# ROMSIMMProgrammer.net
KiCad netlist of a schematic drawn in EAGLE
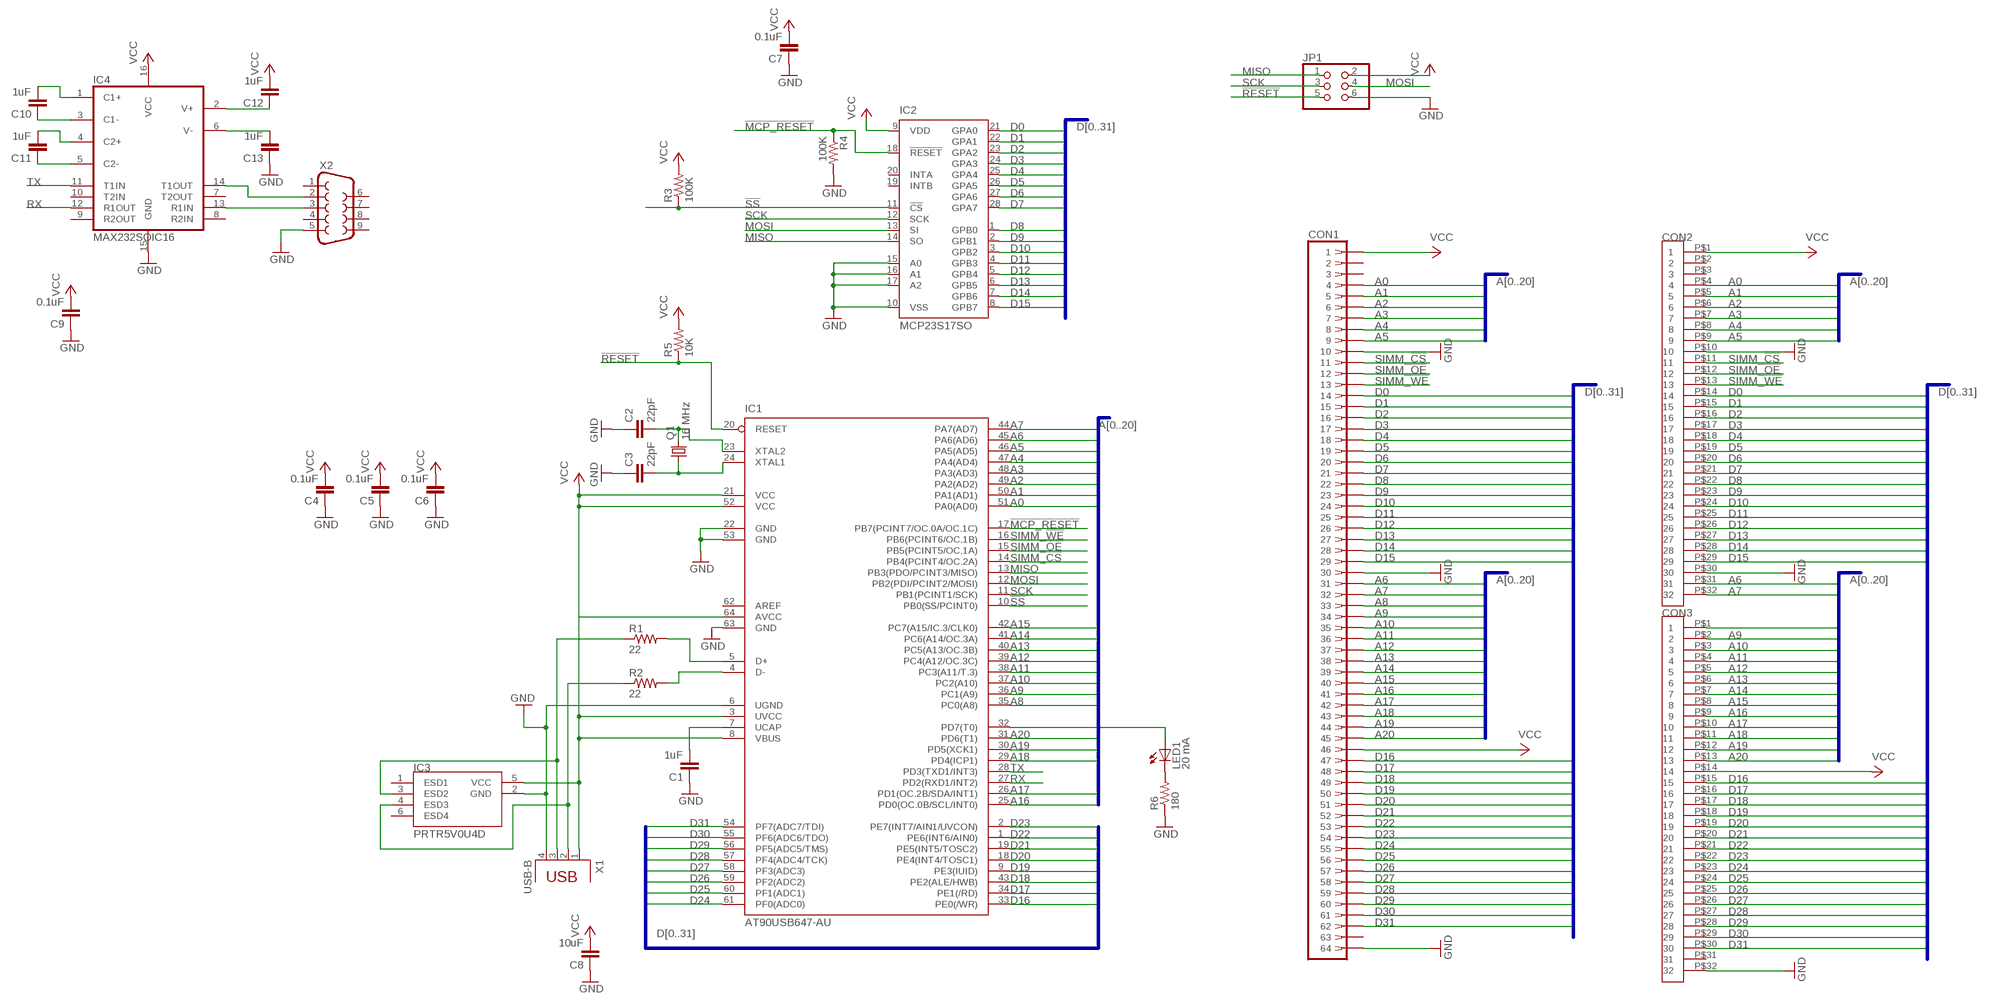
[diagram p0: schematic, sheet 1]

(export (version "E")
  (design (tool "Eeschema 10.0.6"))
  (components
    (comp (ref "C1")
      (value "1uF")
      (footprint "eagle-import:C0805")
      (libsource (lib "eagle-import") (part "C-EUC0805"))
    )
    (comp (ref "C2")
      (value "22pF")
      (footprint "eagle-import:C0805")
      (libsource (lib "eagle-import") (part "C-EUC0805"))
    )
    (comp (ref "C3")
      (value "22pF")
      (footprint "eagle-import:C0805")
      (libsource (lib "eagle-import") (part "C-EUC0805"))
    )
    (comp (ref "C4")
      (value "0.1uF")
      (footprint "eagle-import:C0805")
      (libsource (lib "eagle-import") (part "C-EUC0805"))
    )
    (comp (ref "C5")
      (value "0.1uF")
      (footprint "eagle-import:C0805")
      (libsource (lib "eagle-import") (part "C-EUC0805"))
    )
    (comp (ref "C6")
      (value "0.1uF")
      (footprint "eagle-import:C0805")
      (libsource (lib "eagle-import") (part "C-EUC0805"))
    )
    (comp (ref "C7")
      (value "0.1uF")
      (footprint "eagle-import:C0805")
      (libsource (lib "eagle-import") (part "C-EUC0805"))
    )
    (comp (ref "C8")
      (value "10uF")
      (footprint "eagle-import:C0805")
      (libsource (lib "eagle-import") (part "C-EUC0805"))
    )
    (comp (ref "C9")
      (value "0.1uF")
      (footprint "eagle-import:C0805")
      (libsource (lib "eagle-import") (part "C-EUC0805"))
    )
    (comp (ref "C10")
      (value "1uF")
      (footprint "eagle-import:C0805")
      (libsource (lib "eagle-import") (part "C-EUC0805"))
    )
    (comp (ref "C11")
      (value "1uF")
      (footprint "eagle-import:C0805")
      (libsource (lib "eagle-import") (part "C-EUC0805"))
    )
    (comp (ref "C12")
      (value "1uF")
      (footprint "eagle-import:C0805")
      (libsource (lib "eagle-import") (part "C-EUC0805"))
    )
    (comp (ref "C13")
      (value "1uF")
      (footprint "eagle-import:C0805")
      (libsource (lib "eagle-import") (part "C-EUC0805"))
    )
    (comp (ref "CON1")
      (value "SIMM64")
      (footprint "eagle-import:822032-2")
      (libsource (lib "eagle-import") (part "SIMM64"))
    )
    (comp (ref "CON2")
      (value "SMS-132-01-G-S")
      (footprint "eagle-import:SMS-132-01-G-S")
      (libsource (lib "eagle-import") (part "SMS-132-01-G-S"))
    )
    (comp (ref "CON3")
      (value "SMS-132-01-G-S")
      (footprint "eagle-import:SMS-132-01-G-S")
      (libsource (lib "eagle-import") (part "SMS-132-01-G-S"))
    )
    (comp (ref "IC1")
      (value "AT90USB647-AU")
      (footprint "eagle-import:TQFP64")
      (libsource (lib "eagle-import") (part "AT90USB647-AU"))
    )
    (comp (ref "IC2")
      (value "MCP23S17SO")
      (footprint "eagle-import:SO28W")
      (fields (field (name "MF") "MICROCHIP") (field (name "MPN") "MCP23S17-E/SO"))
      (libsource (lib "eagle-import") (part "MCP23S17SO"))
    )
    (comp (ref "IC3")
      (value "PRTR5V0U4D")
      (footprint "eagle-import:SOT457R_PHILIPS")
      (libsource (lib "eagle-import") (part "PRTR5V0U4D"))
    )
    (comp (ref "IC4")
      (value "MAX232SOIC16")
      (footprint "eagle-import:SO016")
      (libsource (lib "eagle-import") (part "MAX232SOIC16"))
    )
    (comp (ref "JP1")
      (value "PINHD-2X3")
      (footprint "eagle-import:2X03")
      (libsource (lib "eagle-import") (part "PINHD-2X3"))
    )
    (comp (ref "LED1")
      (value "20 mA")
      (footprint "eagle-import:CHIP-LED0805")
      (libsource (lib "eagle-import") (part "LEDCHIP-LED0805"))
    )
    (comp (ref "Q1")
      (value "16 MHz")
      (footprint "eagle-import:HC49UP")
      (libsource (lib "eagle-import") (part "CRYSTALHC49UP"))
    )
    (comp (ref "R1")
      (value "22")
      (footprint "eagle-import:R0805")
      (libsource (lib "eagle-import") (part "R-US_R0805"))
    )
    (comp (ref "R2")
      (value "22")
      (footprint "eagle-import:R0805")
      (libsource (lib "eagle-import") (part "R-US_R0805"))
    )
    (comp (ref "R3")
      (value "100K")
      (footprint "eagle-import:R0805")
      (libsource (lib "eagle-import") (part "R-US_R0805"))
    )
    (comp (ref "R4")
      (value "100K")
      (footprint "eagle-import:R0805")
      (libsource (lib "eagle-import") (part "R-US_R0805"))
    )
    (comp (ref "R5")
      (value "10K")
      (footprint "eagle-import:R0805")
      (libsource (lib "eagle-import") (part "R-US_R0805"))
    )
    (comp (ref "R6")
      (value "180")
      (footprint "eagle-import:R0805")
      (libsource (lib "eagle-import") (part "R-US_R0805"))
    )
    (comp (ref "X1")
      (value "USB-B")
      (footprint "eagle-import:PN61729")
      (libsource (lib "eagle-import") (part "PN61729"))
    )
    (comp (ref "X2")
      (value "DB9FEMALE")
      (footprint "eagle-import:DB9")
      (libsource (lib "eagle-import") (part "DB9FEMALE"))
    )
  )
  (nets
    (net (code "1") (name "/A0") (class "Default")
      (node (ref "CON1") (pin "4") (pinfunction "4_4") (pintype "passive"))
      (node (ref "CON2") (pin "P$4") (pinfunction "4_P$4") (pintype "bidirectional"))
      (node (ref "IC1") (pin "51") (pinfunction "PA0(AD0)_51") (pintype "bidirectional"))
    )
    (net (code "2") (name "/A1") (class "Default")
      (node (ref "CON1") (pin "5") (pinfunction "5_5") (pintype "passive"))
      (node (ref "CON2") (pin "P$5") (pinfunction "5_P$5") (pintype "bidirectional"))
      (node (ref "IC1") (pin "50") (pinfunction "PA1(AD1)_50") (pintype "bidirectional"))
    )
    (net (code "3") (name "/A2") (class "Default")
      (node (ref "CON1") (pin "6") (pinfunction "6_6") (pintype "passive"))
      (node (ref "CON2") (pin "P$6") (pinfunction "6_P$6") (pintype "bidirectional"))
      (node (ref "IC1") (pin "49") (pinfunction "PA2(AD2)_49") (pintype "bidirectional"))
    )
    (net (code "4") (name "/A3") (class "Default")
      (node (ref "CON1") (pin "7") (pinfunction "7_7") (pintype "passive"))
      (node (ref "CON2") (pin "P$7") (pinfunction "7_P$7") (pintype "bidirectional"))
      (node (ref "IC1") (pin "48") (pinfunction "PA3(AD3)_48") (pintype "bidirectional"))
    )
    (net (code "5") (name "/A4") (class "Default")
      (node (ref "CON1") (pin "8") (pinfunction "8_8") (pintype "passive"))
      (node (ref "CON2") (pin "P$8") (pinfunction "8_P$8") (pintype "bidirectional"))
      (node (ref "IC1") (pin "47") (pinfunction "PA4(AD4)_47") (pintype "bidirectional"))
    )
    (net (code "6") (name "/A5") (class "Default")
      (node (ref "CON1") (pin "9") (pinfunction "9_9") (pintype "passive"))
      (node (ref "CON2") (pin "P$9") (pinfunction "9_P$9") (pintype "bidirectional"))
      (node (ref "IC1") (pin "46") (pinfunction "PA5(AD5)_46") (pintype "bidirectional"))
    )
    (net (code "7") (name "/A6") (class "Default")
      (node (ref "CON1") (pin "31") (pinfunction "31_31") (pintype "passive"))
      (node (ref "CON2") (pin "P$31") (pinfunction "31_P$31") (pintype "bidirectional"))
      (node (ref "IC1") (pin "45") (pinfunction "PA6(AD6)_45") (pintype "bidirectional"))
    )
    (net (code "8") (name "/A7") (class "Default")
      (node (ref "CON1") (pin "32") (pinfunction "32_32") (pintype "passive"))
      (node (ref "CON2") (pin "P$32") (pinfunction "32_P$32") (pintype "bidirectional"))
      (node (ref "IC1") (pin "44") (pinfunction "PA7(AD7)_44") (pintype "bidirectional"))
    )
    (net (code "9") (name "/A8") (class "Default")
      (node (ref "CON1") (pin "33") (pinfunction "33_33") (pintype "passive"))
      (node (ref "CON3") (pin "P$1") (pinfunction "1_P$1") (pintype "bidirectional"))
      (node (ref "IC1") (pin "35") (pinfunction "PC0(A8)_35") (pintype "bidirectional"))
    )
    (net (code "10") (name "/A9") (class "Default")
      (node (ref "CON1") (pin "34") (pinfunction "34_34") (pintype "passive"))
      (node (ref "CON3") (pin "P$2") (pinfunction "2_P$2") (pintype "bidirectional"))
      (node (ref "IC1") (pin "36") (pinfunction "PC1(A9)_36") (pintype "bidirectional"))
    )
    (net (code "11") (name "/A10") (class "Default")
      (node (ref "CON1") (pin "35") (pinfunction "35_35") (pintype "passive"))
      (node (ref "CON3") (pin "P$3") (pinfunction "3_P$3") (pintype "bidirectional"))
      (node (ref "IC1") (pin "37") (pinfunction "PC2(A10)_37") (pintype "bidirectional"))
    )
    (net (code "12") (name "/A11") (class "Default")
      (node (ref "CON1") (pin "36") (pinfunction "36_36") (pintype "passive"))
      (node (ref "CON3") (pin "P$4") (pinfunction "4_P$4") (pintype "bidirectional"))
      (node (ref "IC1") (pin "38") (pinfunction "PC3(A11/T.3)_38") (pintype "bidirectional"))
    )
    (net (code "13") (name "/A12") (class "Default")
      (node (ref "CON1") (pin "37") (pinfunction "37_37") (pintype "passive"))
      (node (ref "CON3") (pin "P$5") (pinfunction "5_P$5") (pintype "bidirectional"))
      (node (ref "IC1") (pin "39") (pinfunction "PC4(A12/OC.3C)_39") (pintype "bidirectional"))
    )
    (net (code "14") (name "/A13") (class "Default")
      (node (ref "CON1") (pin "38") (pinfunction "38_38") (pintype "passive"))
      (node (ref "CON3") (pin "P$6") (pinfunction "6_P$6") (pintype "bidirectional"))
      (node (ref "IC1") (pin "40") (pinfunction "PC5(A13/OC.3B)_40") (pintype "bidirectional"))
    )
    (net (code "15") (name "/A14") (class "Default")
      (node (ref "CON1") (pin "39") (pinfunction "39_39") (pintype "passive"))
      (node (ref "CON3") (pin "P$7") (pinfunction "7_P$7") (pintype "bidirectional"))
      (node (ref "IC1") (pin "41") (pinfunction "PC6(A14/OC.3A)_41") (pintype "bidirectional"))
    )
    (net (code "16") (name "/A15") (class "Default")
      (node (ref "CON1") (pin "40") (pinfunction "40_40") (pintype "passive"))
      (node (ref "CON3") (pin "P$8") (pinfunction "8_P$8") (pintype "bidirectional"))
      (node (ref "IC1") (pin "42") (pinfunction "PC7(A15/IC.3/CLK0)_42") (pintype "bidirectional"))
    )
    (net (code "17") (name "/A16") (class "Default")
      (node (ref "CON1") (pin "41") (pinfunction "41_41") (pintype "passive"))
      (node (ref "CON3") (pin "P$9") (pinfunction "9_P$9") (pintype "bidirectional"))
      (node (ref "IC1") (pin "25") (pinfunction "PD0(OC.0B/SCL/INT0)_25") (pintype "bidirectional"))
    )
    (net (code "18") (name "/A17") (class "Default")
      (node (ref "CON1") (pin "42") (pinfunction "42_42") (pintype "passive"))
      (node (ref "CON3") (pin "P$10") (pinfunction "10_P$10") (pintype "bidirectional"))
      (node (ref "IC1") (pin "26") (pinfunction "PD1(OC.2B/SDA/INT1)_26") (pintype "bidirectional"))
    )
    (net (code "19") (name "/A18") (class "Default")
      (node (ref "CON1") (pin "43") (pinfunction "43_43") (pintype "passive"))
      (node (ref "CON3") (pin "P$11") (pinfunction "11_P$11") (pintype "bidirectional"))
      (node (ref "IC1") (pin "29") (pinfunction "PD4(ICP1)_29") (pintype "bidirectional"))
    )
    (net (code "20") (name "/A19") (class "Default")
      (node (ref "CON1") (pin "44") (pinfunction "44_44") (pintype "passive"))
      (node (ref "CON3") (pin "P$12") (pinfunction "12_P$12") (pintype "bidirectional"))
      (node (ref "IC1") (pin "30") (pinfunction "PD5(XCK1)_30") (pintype "bidirectional"))
    )
    (net (code "21") (name "/A20") (class "Default")
      (node (ref "CON1") (pin "45") (pinfunction "45_45") (pintype "passive"))
      (node (ref "CON3") (pin "P$13") (pinfunction "13_P$13") (pintype "bidirectional"))
      (node (ref "IC1") (pin "31") (pinfunction "PD6(T1)_31") (pintype "bidirectional"))
    )
    (net (code "23") (name "/D0") (class "Default")
      (node (ref "CON1") (pin "14") (pinfunction "14_14") (pintype "passive"))
      (node (ref "CON2") (pin "P$14") (pinfunction "14_P$14") (pintype "bidirectional"))
      (node (ref "IC2") (pin "21") (pinfunction "GPA0_21") (pintype "bidirectional"))
    )
    (net (code "24") (name "/D1") (class "Default")
      (node (ref "CON1") (pin "15") (pinfunction "15_15") (pintype "passive"))
      (node (ref "CON2") (pin "P$15") (pinfunction "15_P$15") (pintype "bidirectional"))
      (node (ref "IC2") (pin "22") (pinfunction "GPA1_22") (pintype "bidirectional"))
    )
    (net (code "25") (name "/D2") (class "Default")
      (node (ref "CON1") (pin "16") (pinfunction "16_16") (pintype "passive"))
      (node (ref "CON2") (pin "P$16") (pinfunction "16_P$16") (pintype "bidirectional"))
      (node (ref "IC2") (pin "23") (pinfunction "GPA2_23") (pintype "bidirectional"))
    )
    (net (code "26") (name "/D3") (class "Default")
      (node (ref "CON1") (pin "17") (pinfunction "17_17") (pintype "passive"))
      (node (ref "CON2") (pin "P$17") (pinfunction "17_P$17") (pintype "bidirectional"))
      (node (ref "IC2") (pin "24") (pinfunction "GPA3_24") (pintype "bidirectional"))
    )
    (net (code "27") (name "/D4") (class "Default")
      (node (ref "CON1") (pin "18") (pinfunction "18_18") (pintype "passive"))
      (node (ref "CON2") (pin "P$18") (pinfunction "18_P$18") (pintype "bidirectional"))
      (node (ref "IC2") (pin "25") (pinfunction "GPA4_25") (pintype "bidirectional"))
    )
    (net (code "28") (name "/D5") (class "Default")
      (node (ref "CON1") (pin "19") (pinfunction "19_19") (pintype "passive"))
      (node (ref "CON2") (pin "P$19") (pinfunction "19_P$19") (pintype "bidirectional"))
      (node (ref "IC2") (pin "26") (pinfunction "GPA5_26") (pintype "bidirectional"))
    )
    (net (code "29") (name "/D6") (class "Default")
      (node (ref "CON1") (pin "20") (pinfunction "20_20") (pintype "passive"))
      (node (ref "CON2") (pin "P$20") (pinfunction "20_P$20") (pintype "bidirectional"))
      (node (ref "IC2") (pin "27") (pinfunction "GPA6_27") (pintype "bidirectional"))
    )
    (net (code "30") (name "/D7") (class "Default")
      (node (ref "CON1") (pin "21") (pinfunction "21_21") (pintype "passive"))
      (node (ref "CON2") (pin "P$21") (pinfunction "21_P$21") (pintype "bidirectional"))
      (node (ref "IC2") (pin "28") (pinfunction "GPA7_28") (pintype "bidirectional"))
    )
    (net (code "31") (name "/D8") (class "Default")
      (node (ref "CON1") (pin "22") (pinfunction "22_22") (pintype "passive"))
      (node (ref "CON2") (pin "P$22") (pinfunction "22_P$22") (pintype "bidirectional"))
      (node (ref "IC2") (pin "1") (pinfunction "GPB0_1") (pintype "bidirectional"))
    )
    (net (code "32") (name "/D9") (class "Default")
      (node (ref "CON1") (pin "23") (pinfunction "23_23") (pintype "passive"))
      (node (ref "CON2") (pin "P$23") (pinfunction "23_P$23") (pintype "bidirectional"))
      (node (ref "IC2") (pin "2") (pinfunction "GPB1_2") (pintype "bidirectional"))
    )
    (net (code "33") (name "/D10") (class "Default")
      (node (ref "CON1") (pin "24") (pinfunction "24_24") (pintype "passive"))
      (node (ref "CON2") (pin "P$24") (pinfunction "24_P$24") (pintype "bidirectional"))
      (node (ref "IC2") (pin "3") (pinfunction "GPB2_3") (pintype "bidirectional"))
    )
    (net (code "34") (name "/D11") (class "Default")
      (node (ref "CON1") (pin "25") (pinfunction "25_25") (pintype "passive"))
      (node (ref "CON2") (pin "P$25") (pinfunction "25_P$25") (pintype "bidirectional"))
      (node (ref "IC2") (pin "4") (pinfunction "GPB3_4") (pintype "bidirectional"))
    )
    (net (code "35") (name "/D12") (class "Default")
      (node (ref "CON1") (pin "26") (pinfunction "26_26") (pintype "passive"))
      (node (ref "CON2") (pin "P$26") (pinfunction "26_P$26") (pintype "bidirectional"))
      (node (ref "IC2") (pin "5") (pinfunction "GPB4_5") (pintype "bidirectional"))
    )
    (net (code "36") (name "/D13") (class "Default")
      (node (ref "CON1") (pin "27") (pinfunction "27_27") (pintype "passive"))
      (node (ref "CON2") (pin "P$27") (pinfunction "27_P$27") (pintype "bidirectional"))
      (node (ref "IC2") (pin "6") (pinfunction "GPB5_6") (pintype "bidirectional"))
    )
    (net (code "37") (name "/D14") (class "Default")
      (node (ref "CON1") (pin "28") (pinfunction "28_28") (pintype "passive"))
      (node (ref "CON2") (pin "P$28") (pinfunction "28_P$28") (pintype "bidirectional"))
      (node (ref "IC2") (pin "7") (pinfunction "GPB6_7") (pintype "bidirectional"))
    )
    (net (code "38") (name "/D15") (class "Default")
      (node (ref "CON1") (pin "29") (pinfunction "29_29") (pintype "passive"))
      (node (ref "CON2") (pin "P$29") (pinfunction "29_P$29") (pintype "bidirectional"))
      (node (ref "IC2") (pin "8") (pinfunction "GPB7_8") (pintype "bidirectional"))
    )
    (net (code "39") (name "/D16") (class "Default")
      (node (ref "CON1") (pin "47") (pinfunction "47_47") (pintype "passive"))
      (node (ref "CON3") (pin "P$15") (pinfunction "15_P$15") (pintype "bidirectional"))
      (node (ref "IC1") (pin "33") (pinfunction "PE0(/WR)_33") (pintype "bidirectional"))
    )
    (net (code "40") (name "/D17") (class "Default")
      (node (ref "CON1") (pin "48") (pinfunction "48_48") (pintype "passive"))
      (node (ref "CON3") (pin "P$16") (pinfunction "16_P$16") (pintype "bidirectional"))
      (node (ref "IC1") (pin "34") (pinfunction "PE1(/RD)_34") (pintype "bidirectional"))
    )
    (net (code "41") (name "/D18") (class "Default")
      (node (ref "CON1") (pin "49") (pinfunction "49_49") (pintype "passive"))
      (node (ref "CON3") (pin "P$17") (pinfunction "17_P$17") (pintype "bidirectional"))
      (node (ref "IC1") (pin "43") (pinfunction "PE2(ALE/HWB)_43") (pintype "bidirectional"))
    )
    (net (code "42") (name "/D19") (class "Default")
      (node (ref "CON1") (pin "50") (pinfunction "50_50") (pintype "passive"))
      (node (ref "CON3") (pin "P$18") (pinfunction "18_P$18") (pintype "bidirectional"))
      (node (ref "IC1") (pin "9") (pinfunction "PE3(IUID)_9") (pintype "bidirectional"))
    )
    (net (code "43") (name "/D20") (class "Default")
      (node (ref "CON1") (pin "51") (pinfunction "51_51") (pintype "passive"))
      (node (ref "CON3") (pin "P$19") (pinfunction "19_P$19") (pintype "bidirectional"))
      (node (ref "IC1") (pin "18") (pinfunction "PE4(INT4/TOSC1)_18") (pintype "bidirectional"))
    )
    (net (code "44") (name "/D21") (class "Default")
      (node (ref "CON1") (pin "52") (pinfunction "52_52") (pintype "passive"))
      (node (ref "CON3") (pin "P$20") (pinfunction "20_P$20") (pintype "bidirectional"))
      (node (ref "IC1") (pin "19") (pinfunction "PE5(INT5/TOSC2)_19") (pintype "bidirectional"))
    )
    (net (code "45") (name "/D22") (class "Default")
      (node (ref "CON1") (pin "53") (pinfunction "53_53") (pintype "passive"))
      (node (ref "CON3") (pin "P$21") (pinfunction "21_P$21") (pintype "bidirectional"))
      (node (ref "IC1") (pin "1") (pinfunction "PE6(INT6/AIN0)_1") (pintype "bidirectional"))
    )
    (net (code "46") (name "/D23") (class "Default")
      (node (ref "CON1") (pin "54") (pinfunction "54_54") (pintype "passive"))
      (node (ref "CON3") (pin "P$22") (pinfunction "22_P$22") (pintype "bidirectional"))
      (node (ref "IC1") (pin "2") (pinfunction "PE7(INT7/AIN1/UVCON)_2") (pintype "bidirectional"))
    )
    (net (code "47") (name "/D24") (class "Default")
      (node (ref "CON1") (pin "55") (pinfunction "55_55") (pintype "passive"))
      (node (ref "CON3") (pin "P$23") (pinfunction "23_P$23") (pintype "bidirectional"))
      (node (ref "IC1") (pin "61") (pinfunction "PF0(ADC0)_61") (pintype "bidirectional"))
    )
    (net (code "48") (name "/D25") (class "Default")
      (node (ref "CON1") (pin "56") (pinfunction "56_56") (pintype "passive"))
      (node (ref "CON3") (pin "P$24") (pinfunction "24_P$24") (pintype "bidirectional"))
      (node (ref "IC1") (pin "60") (pinfunction "PF1(ADC1)_60") (pintype "bidirectional"))
    )
    (net (code "49") (name "/D26") (class "Default")
      (node (ref "CON1") (pin "57") (pinfunction "57_57") (pintype "passive"))
      (node (ref "CON3") (pin "P$25") (pinfunction "25_P$25") (pintype "bidirectional"))
      (node (ref "IC1") (pin "59") (pinfunction "PF2(ADC2)_59") (pintype "bidirectional"))
    )
    (net (code "50") (name "/D27") (class "Default")
      (node (ref "CON1") (pin "58") (pinfunction "58_58") (pintype "passive"))
      (node (ref "CON3") (pin "P$26") (pinfunction "26_P$26") (pintype "bidirectional"))
      (node (ref "IC1") (pin "58") (pinfunction "PF3(ADC3)_58") (pintype "bidirectional"))
    )
    (net (code "51") (name "/D28") (class "Default")
      (node (ref "CON1") (pin "59") (pinfunction "59_59") (pintype "passive"))
      (node (ref "CON3") (pin "P$27") (pinfunction "27_P$27") (pintype "bidirectional"))
      (node (ref "IC1") (pin "57") (pinfunction "PF4(ADC4/TCK)_57") (pintype "bidirectional"))
    )
    (net (code "52") (name "/D29") (class "Default")
      (node (ref "CON1") (pin "60") (pinfunction "60_60") (pintype "passive"))
      (node (ref "CON3") (pin "P$28") (pinfunction "28_P$28") (pintype "bidirectional"))
      (node (ref "IC1") (pin "56") (pinfunction "PF5(ADC5/TMS)_56") (pintype "bidirectional"))
    )
    (net (code "53") (name "/D30") (class "Default")
      (node (ref "CON1") (pin "61") (pinfunction "61_61") (pintype "passive"))
      (node (ref "CON3") (pin "P$29") (pinfunction "29_P$29") (pintype "bidirectional"))
      (node (ref "IC1") (pin "55") (pinfunction "PF6(ADC6/TDO)_55") (pintype "bidirectional"))
    )
    (net (code "54") (name "/D31") (class "Default")
      (node (ref "CON1") (pin "62") (pinfunction "62_62") (pintype "passive"))
      (node (ref "CON3") (pin "P$30") (pinfunction "30_P$30") (pintype "bidirectional"))
      (node (ref "IC1") (pin "54") (pinfunction "PF7(ADC7/TDI)_54") (pintype "bidirectional"))
    )
    (net (code "56") (name "/MISO") (class "Default")
      (node (ref "IC1") (pin "13") (pinfunction "PB3(PDO/PCINT3/MISO)_13") (pintype "bidirectional"))
      (node (ref "IC2") (pin "14") (pinfunction "SO_14") (pintype "output"))
      (node (ref "JP1") (pin "1") (pinfunction "1_1") (pintype "passive"))
    )
    (net (code "57") (name "/MOSI") (class "Default")
      (node (ref "IC1") (pin "12") (pinfunction "PB2(PDI/PCINT2/MOSI)_12") (pintype "bidirectional"))
      (node (ref "IC2") (pin "13") (pinfunction "SI_13") (pintype "input"))
      (node (ref "JP1") (pin "4") (pinfunction "4_4") (pintype "passive"))
    )
    (net (code "58") (name "/RX") (class "Default")
      (node (ref "IC1") (pin "27") (pinfunction "PD2(RXD1/INT2)_27") (pintype "bidirectional"))
      (node (ref "IC4") (pin "12") (pinfunction "R1OUT_12") (pintype "output"))
    )
    (net (code "59") (name "/SCK") (class "Default")
      (node (ref "IC1") (pin "11") (pinfunction "PB1(PCINT1/SCK)_11") (pintype "bidirectional"))
      (node (ref "IC2") (pin "12") (pinfunction "SCK_12") (pintype "input"))
      (node (ref "JP1") (pin "3") (pinfunction "3_3") (pintype "passive"))
    )
    (net (code "60") (name "/SIMM_~{CS}") (class "Default")
      (node (ref "CON1") (pin "11") (pinfunction "11_11") (pintype "passive"))
      (node (ref "CON2") (pin "P$11") (pinfunction "11_P$11") (pintype "bidirectional"))
      (node (ref "IC1") (pin "14") (pinfunction "PB4(PCINT4/OC.2A)_14") (pintype "bidirectional"))
    )
    (net (code "61") (name "/SIMM_~{OE}") (class "Default")
      (node (ref "CON1") (pin "12") (pinfunction "12_12") (pintype "passive"))
      (node (ref "CON2") (pin "P$12") (pinfunction "12_P$12") (pintype "bidirectional"))
      (node (ref "IC1") (pin "15") (pinfunction "PB5(PCINT5/OC.1A)_15") (pintype "bidirectional"))
    )
    (net (code "62") (name "/SIMM_~{WE}") (class "Default")
      (node (ref "CON1") (pin "13") (pinfunction "13_13") (pintype "passive"))
      (node (ref "CON2") (pin "P$13") (pinfunction "13_P$13") (pintype "bidirectional"))
      (node (ref "IC1") (pin "16") (pinfunction "PB6(PCINT6/OC.1B)_16") (pintype "bidirectional"))
    )
    (net (code "63") (name "/TX") (class "Default")
      (node (ref "IC1") (pin "28") (pinfunction "PD3(TXD1/INT3)_28") (pintype "bidirectional"))
      (node (ref "IC4") (pin "11") (pinfunction "T1IN_11") (pintype "input"))
    )
    (net (code "64") (name "/~{MCP_RESET}") (class "Default")
      (node (ref "IC1") (pin "17") (pinfunction "PB7(PCINT7/OC.0A/OC.1C)_17") (pintype "bidirectional"))
      (node (ref "IC2") (pin "18") (pinfunction "~{RESET}_18") (pintype "input"))
      (node (ref "R4") (pin "1") (pinfunction "1_1") (pintype "passive"))
    )
    (net (code "65") (name "/~{RESET}") (class "Default")
      (node (ref "IC1") (pin "20") (pinfunction "RESET_20") (pintype "input"))
      (node (ref "JP1") (pin "5") (pinfunction "5_5") (pintype "passive"))
      (node (ref "R5") (pin "1") (pinfunction "1_1") (pintype "passive"))
    )
    (net (code "66") (name "/~{SS}") (class "Default")
      (node (ref "IC1") (pin "10") (pinfunction "PB0(SS/PCINT0)_10") (pintype "bidirectional"))
      (node (ref "IC2") (pin "11") (pinfunction "~{CS}_11") (pintype "input"))
      (node (ref "R3") (pin "1") (pinfunction "1_1") (pintype "passive"))
    )
    (net (code "67") (name "GND") (class "Default")
      (node (ref "C1") (pin "1") (pinfunction "1_1") (pintype "passive"))
      (node (ref "C13") (pin "1") (pinfunction "1_1") (pintype "passive"))
      (node (ref "C2") (pin "1") (pinfunction "1_1") (pintype "passive"))
      (node (ref "C3") (pin "1") (pinfunction "1_1") (pintype "passive"))
      (node (ref "C4") (pin "1") (pinfunction "1_1") (pintype "passive"))
      (node (ref "C5") (pin "1") (pinfunction "1_1") (pintype "passive"))
      (node (ref "C6") (pin "1") (pinfunction "1_1") (pintype "passive"))
      (node (ref "C7") (pin "1") (pinfunction "1_1") (pintype "passive"))
      (node (ref "C8") (pin "1") (pinfunction "1_1") (pintype "passive"))
      (node (ref "C9") (pin "1") (pinfunction "1_1") (pintype "passive"))
      (node (ref "CON1") (pin "10") (pinfunction "10_10") (pintype "passive"))
      (node (ref "CON1") (pin "30") (pinfunction "30_30") (pintype "passive"))
      (node (ref "CON1") (pin "64") (pinfunction "64_64") (pintype "passive"))
      (node (ref "CON2") (pin "P$10") (pinfunction "10_P$10") (pintype "bidirectional"))
      (node (ref "CON2") (pin "P$30") (pinfunction "30_P$30") (pintype "bidirectional"))
      (node (ref "CON3") (pin "P$32") (pinfunction "32_P$32") (pintype "bidirectional"))
      (node (ref "IC1") (pin "22") (pinfunction "GND_22") (pintype "power_in"))
      (node (ref "IC1") (pin "53") (pinfunction "GND_53") (pintype "power_in"))
      (node (ref "IC1") (pin "6") (pinfunction "UGND_6") (pintype "power_in"))
      (node (ref "IC1") (pin "63") (pinfunction "GND_63") (pintype "power_in"))
      (node (ref "IC2") (pin "10") (pinfunction "VSS_10") (pintype "power_in"))
      (node (ref "IC2") (pin "15") (pinfunction "A0_15") (pintype "input"))
      (node (ref "IC2") (pin "16") (pinfunction "A1_16") (pintype "input"))
      (node (ref "IC2") (pin "17") (pinfunction "A2_17") (pintype "input"))
      (node (ref "IC3") (pin "2") (pinfunction "GND_2") (pintype "power_in"))
      (node (ref "IC4") (pin "15") (pinfunction "GND_15") (pintype "bidirectional"))
      (node (ref "JP1") (pin "6") (pinfunction "6_6") (pintype "passive"))
      (node (ref "R4") (pin "2") (pinfunction "2_2") (pintype "passive"))
      (node (ref "R6") (pin "1") (pinfunction "1_1") (pintype "passive"))
      (node (ref "X1") (pin "4") (pinfunction "4_4") (pintype "passive"))
      (node (ref "X2") (pin "5") (pinfunction "5_5") (pintype "passive"))
    )
    (net (code "68") (name "Net-(IC1-D+)") (class "Default")
      (node (ref "IC1") (pin "5") (pinfunction "D+_5") (pintype "bidirectional"))
      (node (ref "R1") (pin "2") (pinfunction "2_2") (pintype "passive"))
    )
    (net (code "69") (name "Net-(IC1-D-)") (class "Default")
      (node (ref "IC1") (pin "4") (pinfunction "D-_4") (pintype "bidirectional"))
      (node (ref "R2") (pin "2") (pinfunction "2_2") (pintype "passive"))
    )
    (net (code "70") (name "Net-(IC1-PD7(T0))") (class "Default")
      (node (ref "IC1") (pin "32") (pinfunction "PD7(T0)_32") (pintype "bidirectional"))
      (node (ref "LED1") (pin "A") (pinfunction "A_A") (pintype "passive"))
    )
    (net (code "71") (name "Net-(IC1-UCAP)") (class "Default")
      (node (ref "C1") (pin "2") (pinfunction "2_2") (pintype "passive"))
      (node (ref "IC1") (pin "7") (pinfunction "UCAP_7") (pintype "power_in"))
    )
    (net (code "72") (name "Net-(IC1-XTAL1)") (class "Default")
      (node (ref "C3") (pin "2") (pinfunction "2_2") (pintype "passive"))
      (node (ref "IC1") (pin "24") (pinfunction "XTAL1_24") (pintype "bidirectional"))
      (node (ref "Q1") (pin "1") (pinfunction "1_1") (pintype "passive"))
    )
    (net (code "73") (name "Net-(IC1-XTAL2)") (class "Default")
      (node (ref "C2") (pin "2") (pinfunction "2_2") (pintype "passive"))
      (node (ref "IC1") (pin "23") (pinfunction "XTAL2_23") (pintype "bidirectional"))
      (node (ref "Q1") (pin "2") (pinfunction "2_2") (pintype "passive"))
    )
    (net (code "74") (name "Net-(IC3-ESD2)") (class "Default")
      (node (ref "IC3") (pin "3") (pinfunction "ESD2_3") (pintype "bidirectional"))
      (node (ref "R1") (pin "1") (pinfunction "1_1") (pintype "passive"))
      (node (ref "X1") (pin "3") (pinfunction "3_3") (pintype "passive"))
    )
    (net (code "75") (name "Net-(IC3-ESD3)") (class "Default")
      (node (ref "IC3") (pin "4") (pinfunction "ESD3_4") (pintype "bidirectional"))
      (node (ref "R2") (pin "1") (pinfunction "1_1") (pintype "passive"))
      (node (ref "X1") (pin "2") (pinfunction "2_2") (pintype "passive"))
    )
    (net (code "76") (name "Net-(IC4-C1+)") (class "Default")
      (node (ref "C10") (pin "2") (pinfunction "2_2") (pintype "passive"))
      (node (ref "IC4") (pin "1") (pinfunction "C1+_1") (pintype "bidirectional"))
    )
    (net (code "77") (name "Net-(IC4-C1-)") (class "Default")
      (node (ref "C10") (pin "1") (pinfunction "1_1") (pintype "passive"))
      (node (ref "IC4") (pin "3") (pinfunction "C1-_3") (pintype "bidirectional"))
    )
    (net (code "78") (name "Net-(IC4-C2+)") (class "Default")
      (node (ref "C11") (pin "2") (pinfunction "2_2") (pintype "passive"))
      (node (ref "IC4") (pin "4") (pinfunction "C2+_4") (pintype "bidirectional"))
    )
    (net (code "79") (name "Net-(IC4-C2-)") (class "Default")
      (node (ref "C11") (pin "1") (pinfunction "1_1") (pintype "passive"))
      (node (ref "IC4") (pin "5") (pinfunction "C2-_5") (pintype "bidirectional"))
    )
    (net (code "80") (name "Net-(IC4-R1IN)") (class "Default")
      (node (ref "IC4") (pin "13") (pinfunction "R1IN_13") (pintype "input"))
      (node (ref "X2") (pin "3") (pinfunction "3_3") (pintype "passive"))
    )
    (net (code "81") (name "Net-(IC4-T1OUT)") (class "Default")
      (node (ref "IC4") (pin "14") (pinfunction "T1OUT_14") (pintype "output"))
      (node (ref "X2") (pin "2") (pinfunction "2_2") (pintype "passive"))
    )
    (net (code "82") (name "Net-(IC4-V+)") (class "Default")
      (node (ref "C12") (pin "1") (pinfunction "1_1") (pintype "passive"))
      (node (ref "IC4") (pin "2") (pinfunction "V+_2") (pintype "bidirectional"))
    )
    (net (code "83") (name "Net-(IC4-V-)") (class "Default")
      (node (ref "C13") (pin "2") (pinfunction "2_2") (pintype "passive"))
      (node (ref "IC4") (pin "6") (pinfunction "V-_6") (pintype "bidirectional"))
    )
    (net (code "84") (name "Net-(LED1-PadC)") (class "Default")
      (node (ref "LED1") (pin "C") (pinfunction "C_C") (pintype "passive"))
      (node (ref "R6") (pin "2") (pinfunction "2_2") (pintype "passive"))
    )
    (net (code "85") (name "VCC") (class "Default")
      (node (ref "C12") (pin "2") (pinfunction "2_2") (pintype "passive"))
      (node (ref "C4") (pin "2") (pinfunction "2_2") (pintype "passive"))
      (node (ref "C5") (pin "2") (pinfunction "2_2") (pintype "passive"))
      (node (ref "C6") (pin "2") (pinfunction "2_2") (pintype "passive"))
      (node (ref "C7") (pin "2") (pinfunction "2_2") (pintype "passive"))
      (node (ref "C8") (pin "2") (pinfunction "2_2") (pintype "passive"))
      (node (ref "C9") (pin "2") (pinfunction "2_2") (pintype "passive"))
      (node (ref "CON1") (pin "1") (pinfunction "1_1") (pintype "passive"))
      (node (ref "CON1") (pin "46") (pinfunction "46_46") (pintype "passive"))
      (node (ref "CON2") (pin "P$1") (pinfunction "1_P$1") (pintype "bidirectional"))
      (node (ref "CON3") (pin "P$14") (pinfunction "14_P$14") (pintype "bidirectional"))
      (node (ref "IC1") (pin "21") (pinfunction "VCC_21") (pintype "power_in"))
      (node (ref "IC1") (pin "3") (pinfunction "UVCC_3") (pintype "power_in"))
      (node (ref "IC1") (pin "52") (pinfunction "VCC_52") (pintype "power_in"))
      (node (ref "IC1") (pin "64") (pinfunction "AVCC_64") (pintype "bidirectional"))
      (node (ref "IC1") (pin "8") (pinfunction "VBUS_8") (pintype "power_in"))
      (node (ref "IC2") (pin "9") (pinfunction "VDD_9") (pintype "power_in"))
      (node (ref "IC3") (pin "5") (pinfunction "VCC_5") (pintype "power_in"))
      (node (ref "IC4") (pin "16") (pinfunction "VCC_16") (pintype "bidirectional"))
      (node (ref "JP1") (pin "2") (pinfunction "2_2") (pintype "passive"))
      (node (ref "R3") (pin "2") (pinfunction "2_2") (pintype "passive"))
      (node (ref "R5") (pin "2") (pinfunction "2_2") (pintype "passive"))
      (node (ref "X1") (pin "1") (pinfunction "1_1") (pintype "passive"))
    )
    (net (code "86") (name "unconnected-(CON1-Pad2)") (class "Default")
      (node (ref "CON1") (pin "2") (pinfunction "2_2") (pintype "passive"))
    )
    (net (code "87") (name "unconnected-(CON1-Pad3)") (class "Default")
      (node (ref "CON1") (pin "3") (pinfunction "3_3") (pintype "passive"))
    )
    (net (code "88") (name "unconnected-(CON1-Pad63)") (class "Default")
      (node (ref "CON1") (pin "63") (pinfunction "63_63") (pintype "passive"))
    )
    (net (code "89") (name "unconnected-(CON2-2-PadP$2)") (class "Default")
      (node (ref "CON2") (pin "P$2") (pinfunction "2_P$2") (pintype "bidirectional"))
    )
    (net (code "90") (name "unconnected-(CON2-3-PadP$3)") (class "Default")
      (node (ref "CON2") (pin "P$3") (pinfunction "3_P$3") (pintype "bidirectional"))
    )
    (net (code "91") (name "unconnected-(CON3-31-PadP$31)") (class "Default")
      (node (ref "CON3") (pin "P$31") (pinfunction "31_P$31") (pintype "bidirectional"))
    )
    (net (code "92") (name "unconnected-(IC1-AREF-Pad62)") (class "Default")
      (node (ref "IC1") (pin "62") (pinfunction "AREF_62") (pintype "bidirectional"))
    )
    (net (code "93") (name "unconnected-(IC2-INTA-Pad20)") (class "Default")
      (node (ref "IC2") (pin "20") (pinfunction "INTA_20") (pintype "output"))
    )
    (net (code "94") (name "unconnected-(IC2-INTB-Pad19)") (class "Default")
      (node (ref "IC2") (pin "19") (pinfunction "INTB_19") (pintype "output"))
    )
    (net (code "95") (name "unconnected-(IC3-ESD1-Pad1)") (class "Default")
      (node (ref "IC3") (pin "1") (pinfunction "ESD1_1") (pintype "bidirectional"))
    )
    (net (code "96") (name "unconnected-(IC3-ESD4-Pad6)") (class "Default")
      (node (ref "IC3") (pin "6") (pinfunction "ESD4_6") (pintype "bidirectional"))
    )
    (net (code "97") (name "unconnected-(IC4-R2IN-Pad8)") (class "Default")
      (node (ref "IC4") (pin "8") (pinfunction "R2IN_8") (pintype "input"))
    )
    (net (code "98") (name "unconnected-(IC4-R2OUT-Pad9)") (class "Default")
      (node (ref "IC4") (pin "9") (pinfunction "R2OUT_9") (pintype "output"))
    )
    (net (code "99") (name "unconnected-(IC4-T2IN-Pad10)") (class "Default")
      (node (ref "IC4") (pin "10") (pinfunction "T2IN_10") (pintype "input"))
    )
    (net (code "100") (name "unconnected-(IC4-T2OUT-Pad7)") (class "Default")
      (node (ref "IC4") (pin "7") (pinfunction "T2OUT_7") (pintype "output"))
    )
    (net (code "101") (name "unconnected-(X2-Pad1)") (class "Default")
      (node (ref "X2") (pin "1") (pinfunction "1_1") (pintype "passive"))
    )
    (net (code "102") (name "unconnected-(X2-Pad4)") (class "Default")
      (node (ref "X2") (pin "4") (pinfunction "4_4") (pintype "passive"))
    )
    (net (code "103") (name "unconnected-(X2-Pad6)") (class "Default")
      (node (ref "X2") (pin "6") (pinfunction "6_6") (pintype "passive"))
    )
    (net (code "104") (name "unconnected-(X2-Pad7)") (class "Default")
      (node (ref "X2") (pin "7") (pinfunction "7_7") (pintype "passive"))
    )
    (net (code "105") (name "unconnected-(X2-Pad8)") (class "Default")
      (node (ref "X2") (pin "8") (pinfunction "8_8") (pintype "passive"))
    )
    (net (code "106") (name "unconnected-(X2-Pad9)") (class "Default")
      (node (ref "X2") (pin "9") (pinfunction "9_9") (pintype "passive"))
    )
  )
)
